# 3-RT5572-WLAN.net
KiCad netlist of a schematic drawn in Altium Designer
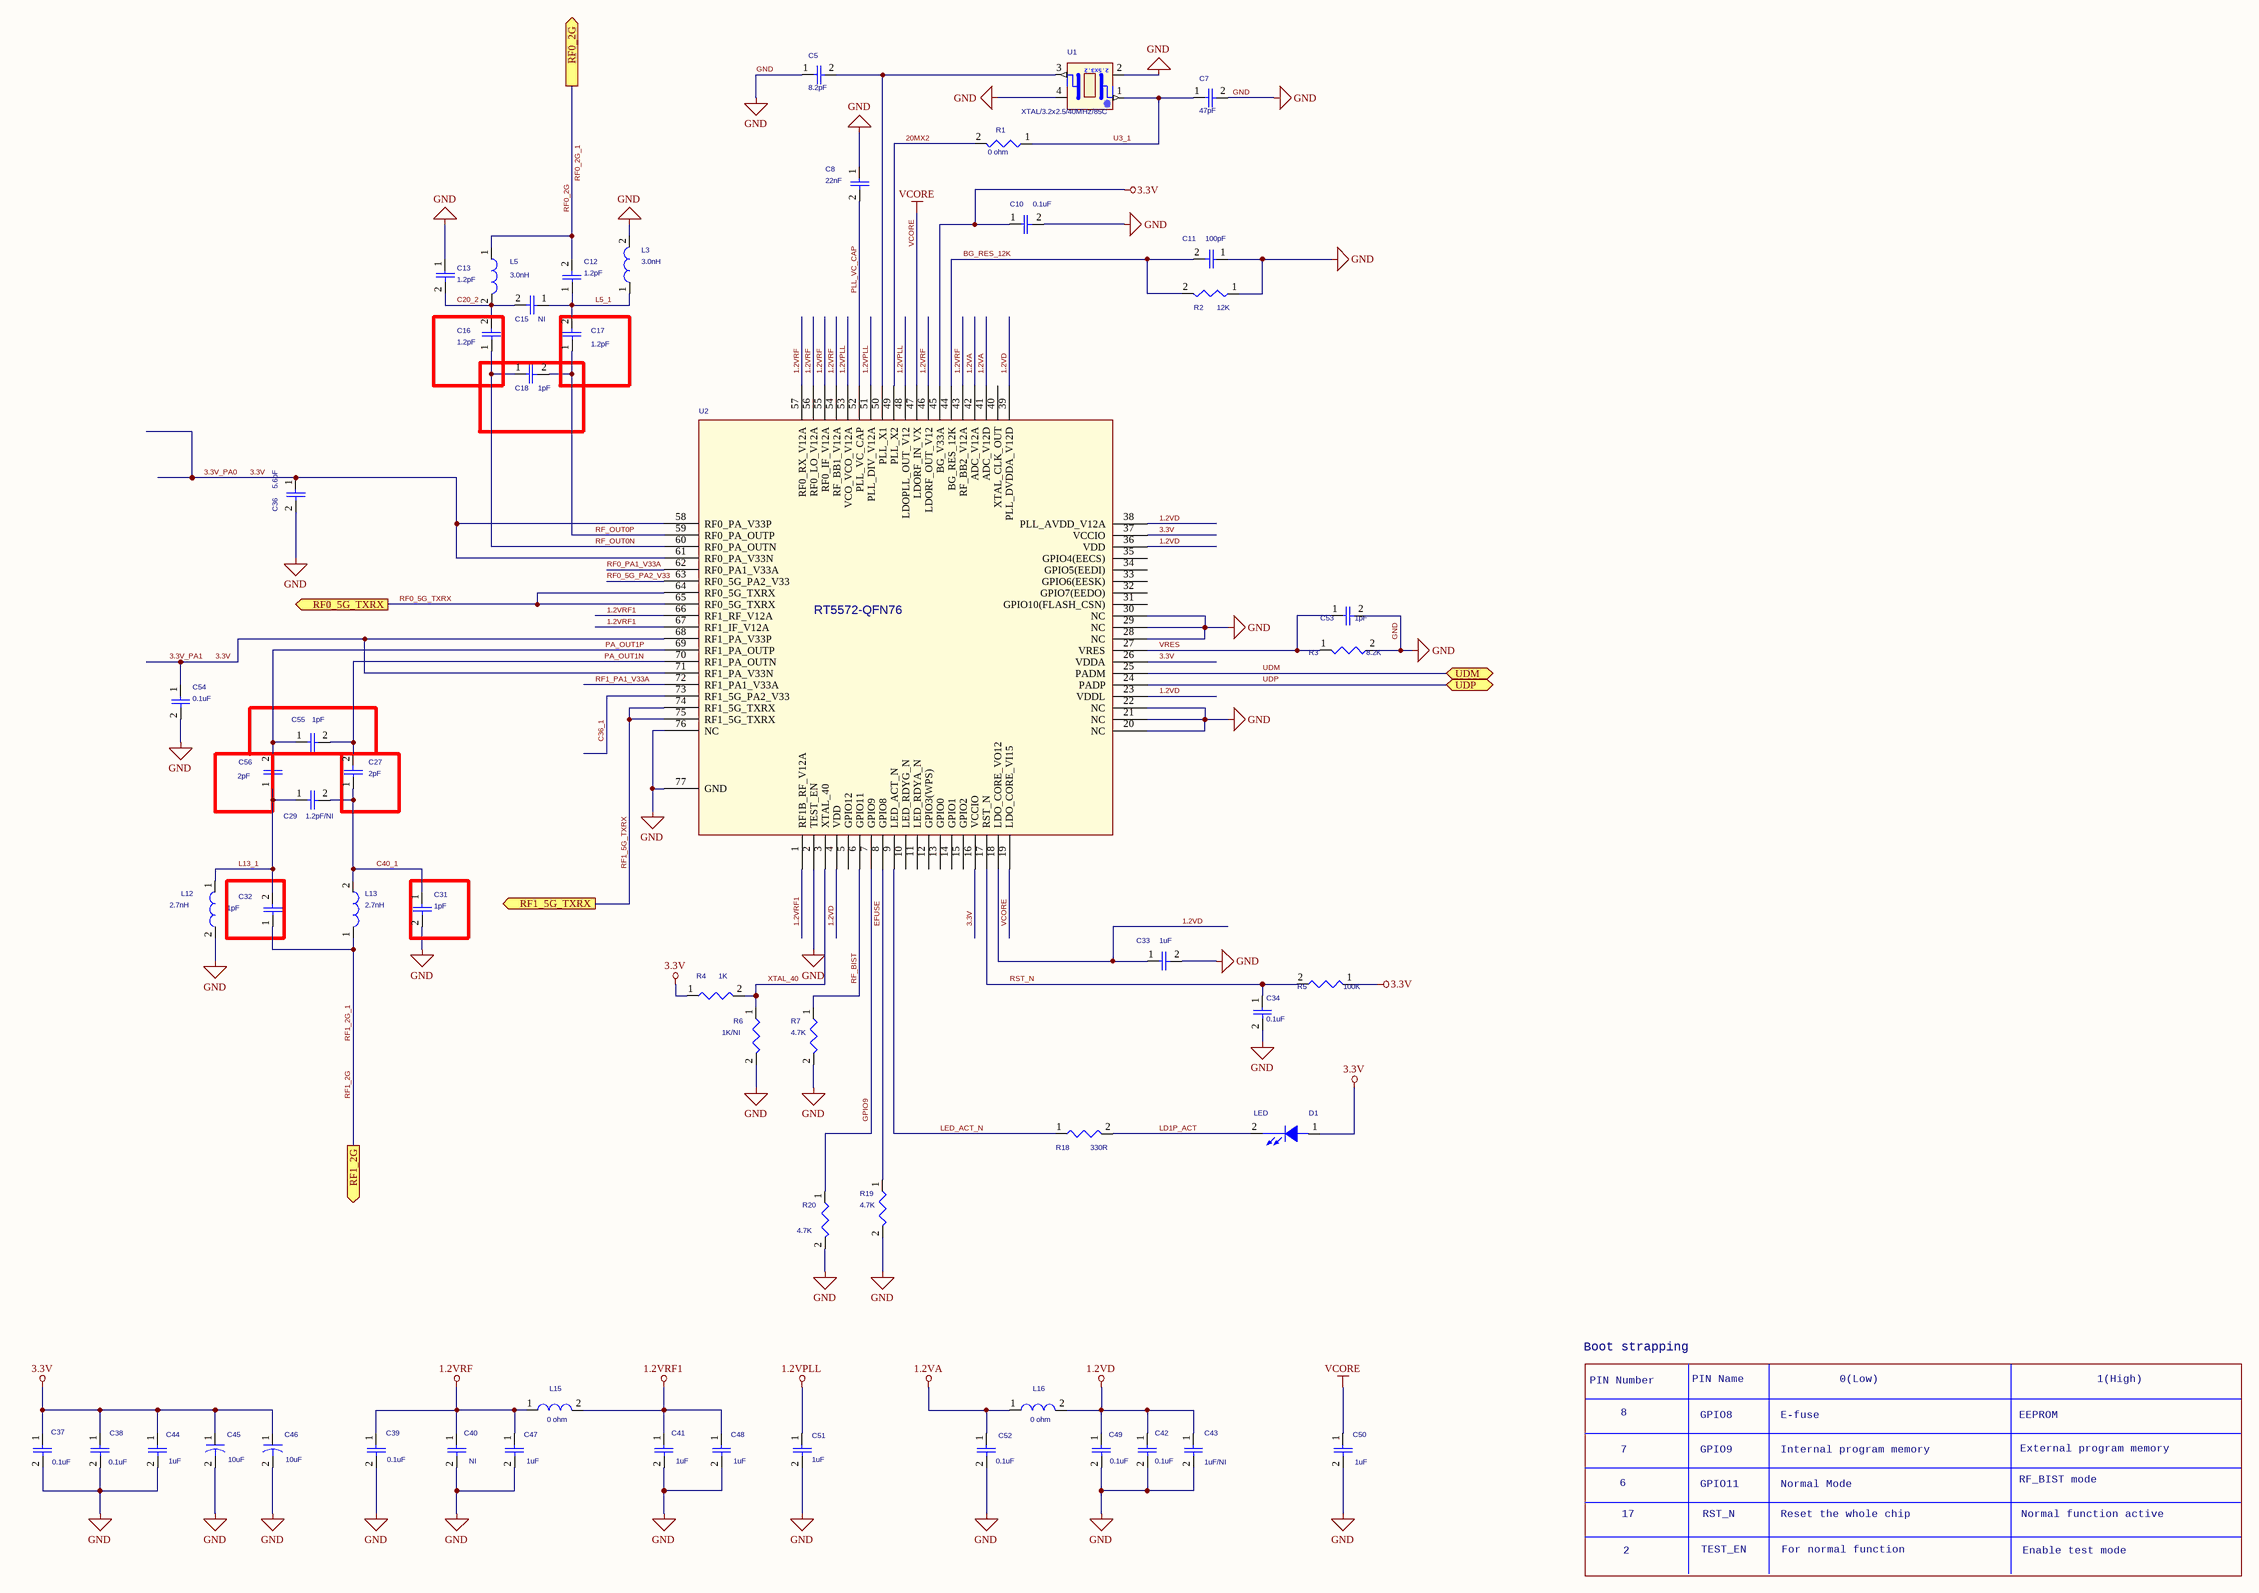
[diagram p0: 3-RT5572-WLAN.SchDoc]

(export (version "E")
  (design (tool "Eeschema 10.0.6"))
  (components
    (comp (ref "C5") (value "8.2pF") (footprint "0402") (libsource (lib "*") (part "CAP/0402")))
    (comp (ref "C7") (value "47pF") (footprint "0402") (libsource (lib "*") (part "CAP/0402")))
    (comp (ref "C8") (value "22nF") (footprint "0402") (libsource (lib "*") (part "CAP/0402")))
    (comp (ref "C10") (value "0.1uF") (footprint "0402") (libsource (lib "*") (part "CAP/0402")))
    (comp (ref "C11") (value "100pF") (footprint "0402") (libsource (lib "*") (part "CAP/0402")))
    (comp (ref "C12") (value "1.2pF") (footprint "0402") (libsource (lib "*") (part "CAP/0402")))
    (comp (ref "C13") (value "1.2pF") (footprint "0402") (libsource (lib "*") (part "CAP/0402")))
    (comp (ref "C15") (value "NI") (footprint "0402") (libsource (lib "*") (part "CAP/0402")))
    (comp (ref "C16") (value "1.2pF") (footprint "0402") (libsource (lib "*") (part "CAP/0402")))
    (comp (ref "C17") (value "1.2pF") (footprint "0402") (libsource (lib "*") (part "CAP/0402")))
    (comp (ref "C18") (value "1pF") (footprint "0402") (libsource (lib "*") (part "CAP/0402")))
    (comp (ref "C27") (value "2pF") (footprint "0402") (libsource (lib "*") (part "CAP/0402")))
    (comp (ref "C29") (value "1.2pF/NI") (footprint "0402") (libsource (lib "*") (part "CAP/0402")))
    (comp (ref "C31") (value "1pF") (footprint "0402") (libsource (lib "*") (part "CAP/0402")))
    (comp (ref "C32") (value "1pF") (footprint "0402") (libsource (lib "*") (part "CAP/0402")))
    (comp (ref "C33") (value "1uF") (footprint "0402") (libsource (lib "*") (part "CAP/0402")))
    (comp (ref "C34") (value "0.1uF") (footprint "0402") (libsource (lib "*") (part "CAP/0402")))
    (comp (ref "C36") (value "5.6pF") (footprint "0402") (libsource (lib "*") (part "CAP/0402")))
    (comp (ref "C37") (value "0.1uF") (footprint "0402") (libsource (lib "*") (part "CAP/0402")))
    (comp (ref "C38") (value "0.1uF") (footprint "0402") (libsource (lib "*") (part "CAP/0402")))
    (comp (ref "C39") (value "0.1uF") (footprint "0402") (libsource (lib "*") (part "CAP/0402")))
    (comp (ref "C40") (value "NI") (footprint "0402") (libsource (lib "*") (part "CAP/0402")))
    (comp (ref "C41") (value "1uF") (footprint "0402") (libsource (lib "*") (part "CAP/0402")))
    (comp (ref "C42") (value "0.1uF") (footprint "0402") (libsource (lib "*") (part "CAP/0402")))
    (comp (ref "C43") (value "1uF/NI") (footprint "0402") (libsource (lib "*") (part "CAP/0402")))
    (comp (ref "C44") (value "1uF") (footprint "0402") (libsource (lib "*") (part "CAP/0402")))
    (comp (ref "C45") (value "10uF") (libsource (lib "*") (part "CAP/0603")))
    (comp (ref "C46") (value "10uF") (libsource (lib "*") (part "CAP/0603")))
    (comp (ref "C47") (value "1uF") (footprint "0402") (libsource (lib "*") (part "CAP/0402")))
    (comp (ref "C48") (value "1uF") (footprint "0402") (libsource (lib "*") (part "CAP/0402")))
    (comp (ref "C49") (value "0.1uF") (footprint "0402") (libsource (lib "*") (part "CAP/0402")))
    (comp (ref "C50") (value "1uF") (footprint "0402") (libsource (lib "*") (part "CAP/0402")))
    (comp (ref "C51") (value "1uF") (footprint "0402") (libsource (lib "*") (part "CAP/0402")))
    (comp (ref "C52") (value "0.1uF") (footprint "0402") (libsource (lib "*") (part "CAP/0402")))
    (comp (ref "C53") (value "1pF") (footprint "0402") (libsource (lib "*") (part "CAP/0402")))
    (comp (ref "C54") (value "0.1uF") (footprint "0402") (libsource (lib "*") (part "CAP/0402")))
    (comp (ref "C55") (value "1pF") (footprint "0402") (libsource (lib "*") (part "CAP/0402")))
    (comp (ref "C56") (value "2pF") (footprint "0402") (libsource (lib "*") (part "CAP/0402")))
    (comp (ref "D1") (value "LED") (footprint "0603") (libsource (lib "*") (part "LED/0603")))
    (comp (ref "L3") (value "3.0nH") (footprint "0402") (libsource (lib "") (part "L/0402_1")))
    (comp (ref "L5") (value "3.0nH") (footprint "0402") (libsource (lib "") (part "L/0402_1")))
    (comp (ref "L12") (value "2.7nH") (footprint "0402") (libsource (lib "*") (part "L/0402_0")))
    (comp (ref "L13") (value "2.7nH") (footprint "0402") (libsource (lib "*") (part "L/0402")))
    (comp (ref "L15") (value "0 ohm") (footprint "0402") (libsource (lib "") (part "L/0402_1")))
    (comp (ref "L16") (value "0 ohm") (footprint "0402") (libsource (lib "") (part "L/0402_1")))
    (comp (ref "R1") (value "0 ohm") (footprint "0402") (libsource (lib "*") (part "RES/0402_1_Dup1")))
    (comp (ref "R2") (value "12K") (footprint "0402") (libsource (lib "*") (part "RES/0402_1_Dup1")))
    (comp (ref "R3") (value "8.2K") (footprint "0402") (libsource (lib "*") (part "RES/0402_2")))
    (comp (ref "R4") (value "1K") (footprint "0402") (libsource (lib "*") (part "RES/0402_1_Dup2")))
    (comp (ref "R5") (value "100K") (footprint "0402") (libsource (lib "*") (part "RES/0402_1_Dup1")))
    (comp (ref "R6") (value "1K/NI") (footprint "0402") (libsource (lib "*") (part "RES/0402_1_Dup2")))
    (comp (ref "R7") (value "4.7K") (footprint "0402") (libsource (lib "*") (part "RES/0402_1_Dup2")))
    (comp (ref "R18") (value "330R") (footprint "0402") (libsource (lib "*") (part "RES/0402_1")))
    (comp (ref "R19") (value "4.7K") (footprint "0402") (libsource (lib "*") (part "RES/0402_1_Dup2")))
    (comp (ref "R20") (value "4.7K") (footprint "0402") (libsource (lib "*") (part "RES/0402_1_Dup2")))
    (comp (ref "U1")
      (value "XTAL/3.2x2.5/40MHz/85C")
      (footprint "XTAL-SMD/3.2X2.5")
      (libsource (lib "*") (part "XTAL_2.5"))
    )
    (comp (ref "U2") (value "RT5572-QFN76") (libsource (lib "*") (part "RT5572_5")))
  )
  (nets
    (net (code "1") (name "/20MX2") (class "Default")
      (node (ref "R1") (pin "2") (pinfunction "2_2") (pintype "passive"))
      (node (ref "U2") (pin "49") (pinfunction "PLL_X2_49") (pintype "passive"))
    )
    (net (code "2") (name "/BG_RES_12K") (class "Default")
      (node (ref "C11") (pin "2") (pinfunction "2_2") (pintype "passive"))
      (node (ref "R2") (pin "2") (pinfunction "2_2") (pintype "passive"))
      (node (ref "U2") (pin "44") (pinfunction "BG_RES_12K_44") (pintype "passive"))
    )
    (net (code "3") (name "/C20_2") (class "Default")
      (node (ref "C13") (pin "2") (pinfunction "2_2") (pintype "passive"))
      (node (ref "C15") (pin "2") (pinfunction "2_2") (pintype "passive"))
      (node (ref "C16") (pin "2") (pinfunction "2_2") (pintype "passive"))
      (node (ref "L5") (pin "2") (pinfunction "2_2") (pintype "passive"))
    )
    (net (code "4") (name "/C36_1") (class "Default")
      (node (ref "U2") (pin "73") (pinfunction "RF1_5G_PA2_V33_73") (pintype "passive"))
    )
    (net (code "5") (name "/C40_1") (class "Default")
      (node (ref "C27") (pin "1") (pinfunction "1_1") (pintype "passive"))
      (node (ref "C29") (pin "2") (pinfunction "2_2") (pintype "passive"))
      (node (ref "C31") (pin "1") (pinfunction "1_1") (pintype "passive"))
      (node (ref "L13") (pin "2") (pinfunction "2_2") (pintype "passive"))
    )
    (net (code "6") (name "/EFUSE") (class "Default")
      (node (ref "R19") (pin "1") (pinfunction "1_1") (pintype "passive"))
      (node (ref "U2") (pin "8") (pinfunction "GPIO8_8") (pintype "passive"))
    )
    (net (code "7") (name "/GPIO9") (class "Default")
      (node (ref "R20") (pin "1") (pinfunction "1_1") (pintype "passive"))
      (node (ref "U2") (pin "7") (pinfunction "GPIO9_7") (pintype "passive"))
    )
    (net (code "8") (name "/L5_1") (class "Default")
      (node (ref "C12") (pin "1") (pinfunction "1_1") (pintype "passive"))
      (node (ref "C15") (pin "1") (pinfunction "1_1") (pintype "passive"))
      (node (ref "C17") (pin "2") (pinfunction "2_2") (pintype "passive"))
      (node (ref "L3") (pin "1") (pinfunction "1_1") (pintype "passive"))
    )
    (net (code "9") (name "/L13_1") (class "Default")
      (node (ref "C29") (pin "1") (pinfunction "1_1") (pintype "passive"))
      (node (ref "C32") (pin "2") (pinfunction "2_2") (pintype "passive"))
      (node (ref "C56") (pin "1") (pinfunction "1_1") (pintype "passive"))
      (node (ref "L12") (pin "1") (pinfunction "1_1") (pintype "passive"))
    )
    (net (code "10") (name "/LD1P_ACT") (class "Default")
      (node (ref "D1") (pin "2") (pinfunction "CATHODE_2") (pintype "passive"))
      (node (ref "R18") (pin "2") (pinfunction "2_2") (pintype "passive"))
    )
    (net (code "11") (name "/LED_ACT_N") (class "Default")
      (node (ref "R18") (pin "1") (pinfunction "1_1") (pintype "passive"))
      (node (ref "U2") (pin "9") (pinfunction "LED_ACT_N_9") (pintype "passive"))
    )
    (net (code "12") (name "/PA_OUT1N") (class "Default")
      (node (ref "C27") (pin "2") (pinfunction "2_2") (pintype "passive"))
      (node (ref "C55") (pin "2") (pinfunction "2_2") (pintype "passive"))
      (node (ref "U2") (pin "70") (pinfunction "RF1_PA_OUTN_70") (pintype "passive"))
    )
    (net (code "13") (name "/PA_OUT1P") (class "Default")
      (node (ref "C55") (pin "1") (pinfunction "1_1") (pintype "passive"))
      (node (ref "C56") (pin "2") (pinfunction "2_2") (pintype "passive"))
      (node (ref "U2") (pin "69") (pinfunction "RF1_PA_OUTP_69") (pintype "passive"))
    )
    (net (code "14") (name "/PLL_VC_CAP") (class "Default")
      (node (ref "C8") (pin "2") (pinfunction "2_2") (pintype "passive"))
      (node (ref "U2") (pin "52") (pinfunction "PLL_VC_CAP_52") (pintype "passive"))
    )
    (net (code "15") (name "/RF0_2G") (class "Default")
      (node (ref "C12") (pin "2") (pinfunction "2_2") (pintype "passive"))
      (node (ref "L5") (pin "1") (pinfunction "1_1") (pintype "passive"))
    )
    (net (code "16") (name "/RF0_5G_PA2_V33") (class "Default")
      (node (ref "U2") (pin "63") (pinfunction "RF0_5G_PA2_V33_63") (pintype "passive"))
    )
    (net (code "17") (name "/RF0_5G_TXRX") (class "Default")
      (node (ref "U2") (pin "64") (pinfunction "RF0_5G_TXRX_64") (pintype "passive"))
      (node (ref "U2") (pin "65") (pinfunction "RF0_5G_TXRX_65") (pintype "passive"))
    )
    (net (code "18") (name "/RF0_PA1_V33A") (class "Default")
      (node (ref "U2") (pin "62") (pinfunction "RF0_PA1_V33A_62") (pintype "passive"))
    )
    (net (code "19") (name "/RF1_2G") (class "Default")
      (node (ref "C32") (pin "1") (pinfunction "1_1") (pintype "passive"))
      (node (ref "L13") (pin "1") (pinfunction "1_1") (pintype "passive"))
    )
    (net (code "20") (name "/RF1_5G_TXRX") (class "Default")
      (node (ref "U2") (pin "74") (pinfunction "RF1_5G_TXRX_74") (pintype "passive"))
      (node (ref "U2") (pin "75") (pinfunction "RF1_5G_TXRX_75") (pintype "passive"))
    )
    (net (code "21") (name "/RF1_PA1_V33A") (class "Default")
      (node (ref "U2") (pin "72") (pinfunction "RF1_PA1_V33A_72") (pintype "passive"))
    )
    (net (code "22") (name "/RF_BIST") (class "Default")
      (node (ref "R7") (pin "1") (pinfunction "1_1") (pintype "passive"))
      (node (ref "U2") (pin "6") (pinfunction "GPIO11_6") (pintype "passive"))
    )
    (net (code "23") (name "/RF_OUT0N") (class "Default")
      (node (ref "C16") (pin "1") (pinfunction "1_1") (pintype "passive"))
      (node (ref "C18") (pin "1") (pinfunction "1_1") (pintype "passive"))
      (node (ref "U2") (pin "60") (pinfunction "RF0_PA_OUTN_60") (pintype "passive"))
    )
    (net (code "24") (name "/RF_OUT0P") (class "Default")
      (node (ref "C17") (pin "1") (pinfunction "1_1") (pintype "passive"))
      (node (ref "C18") (pin "2") (pinfunction "2_2") (pintype "passive"))
      (node (ref "U2") (pin "59") (pinfunction "RF0_PA_OUTP_59") (pintype "passive"))
    )
    (net (code "25") (name "/RST_N") (class "Default")
      (node (ref "C34") (pin "1") (pinfunction "1_1") (pintype "passive"))
      (node (ref "R5") (pin "2") (pinfunction "2_2") (pintype "passive"))
      (node (ref "U2") (pin "17") (pinfunction "RST_N_17") (pintype "passive"))
    )
    (net (code "26") (name "/U3_1") (class "Default")
      (node (ref "C7") (pin "1") (pinfunction "1_1") (pintype "passive"))
      (node (ref "R1") (pin "1") (pinfunction "1_1") (pintype "passive"))
      (node (ref "U1") (pin "1") (pinfunction "X1_1") (pintype "output"))
    )
    (net (code "27") (name "/UDM") (class "Default")
      (node (ref "U2") (pin "25") (pinfunction "PADM_25") (pintype "passive"))
    )
    (net (code "28") (name "/UDP") (class "Default")
      (node (ref "U2") (pin "24") (pinfunction "PADP_24") (pintype "passive"))
    )
    (net (code "29") (name "/VRES") (class "Default")
      (node (ref "C53") (pin "1") (pinfunction "1_1") (pintype "passive"))
      (node (ref "R3") (pin "1") (pinfunction "1_1") (pintype "passive"))
      (node (ref "U2") (pin "27") (pinfunction "VRES_27") (pintype "passive"))
    )
    (net (code "30") (name "/XTAL_40") (class "Default")
      (node (ref "R4") (pin "2") (pinfunction "2_2") (pintype "passive"))
      (node (ref "R6") (pin "1") (pinfunction "1_1") (pintype "passive"))
      (node (ref "U2") (pin "3") (pinfunction "XTAL_40_3") (pintype "passive"))
    )
    (net (code "31") (name "1.2VA") (class "Default")
      (node (ref "C52") (pin "1") (pinfunction "1_1") (pintype "passive"))
      (node (ref "L16") (pin "1") (pinfunction "1_1") (pintype "passive"))
      (node (ref "U2") (pin "41") (pinfunction "ADC_V12D_41") (pintype "passive"))
      (node (ref "U2") (pin "42") (pinfunction "ADC_V12A_42") (pintype "passive"))
    )
    (net (code "32") (name "1.2VD") (class "Default")
      (node (ref "C33") (pin "1") (pinfunction "1_1") (pintype "passive"))
      (node (ref "C42") (pin "1") (pinfunction "1_1") (pintype "passive"))
      (node (ref "C43") (pin "1") (pinfunction "1_1") (pintype "passive"))
      (node (ref "C49") (pin "1") (pinfunction "1_1") (pintype "passive"))
      (node (ref "L16") (pin "2") (pinfunction "2_2") (pintype "passive"))
      (node (ref "U2") (pin "18") (pinfunction "LDO_CORE_VO12_18") (pintype "passive"))
      (node (ref "U2") (pin "23") (pinfunction "VDDL_23") (pintype "passive"))
      (node (ref "U2") (pin "36") (pinfunction "VDD_36") (pintype "passive"))
      (node (ref "U2") (pin "38") (pinfunction "PLL_AVDD_V12A_38") (pintype "passive"))
      (node (ref "U2") (pin "39") (pinfunction "PLL_DVDDA_V12D_39") (pintype "passive"))
      (node (ref "U2") (pin "4") (pinfunction "VDD_4") (pintype "passive"))
    )
    (net (code "33") (name "1.2VPLL") (class "Default")
      (node (ref "C51") (pin "1") (pinfunction "1_1") (pintype "passive"))
      (node (ref "U2") (pin "48") (pinfunction "LDOPLL_OUT_V12_48") (pintype "passive"))
      (node (ref "U2") (pin "51") (pinfunction "PLL_DIV_V12A_51") (pintype "passive"))
      (node (ref "U2") (pin "53") (pinfunction "VCO_VCO_V12A_53") (pintype "passive"))
    )
    (net (code "34") (name "1.2VRF") (class "Default")
      (node (ref "C39") (pin "1") (pinfunction "1_1") (pintype "passive"))
      (node (ref "C40") (pin "1") (pinfunction "1_1") (pintype "passive"))
      (node (ref "C47") (pin "1") (pinfunction "1_1") (pintype "passive"))
      (node (ref "L15") (pin "1") (pinfunction "1_1") (pintype "passive"))
      (node (ref "U2") (pin "43") (pinfunction "RF_BB2_V12A_43") (pintype "passive"))
      (node (ref "U2") (pin "46") (pinfunction "LDORF_OUT_V12_46") (pintype "passive"))
      (node (ref "U2") (pin "54") (pinfunction "RF_BB1_V12A_54") (pintype "passive"))
      (node (ref "U2") (pin "55") (pinfunction "RF0_IF_V12A_55") (pintype "passive"))
      (node (ref "U2") (pin "56") (pinfunction "RF0_LO_V12A_56") (pintype "passive"))
      (node (ref "U2") (pin "57") (pinfunction "RF0_RX_V12A_57") (pintype "passive"))
    )
    (net (code "35") (name "1.2VRF1") (class "Default")
      (node (ref "C41") (pin "1") (pinfunction "1_1") (pintype "passive"))
      (node (ref "C48") (pin "1") (pinfunction "1_1") (pintype "passive"))
      (node (ref "L15") (pin "2") (pinfunction "2_2") (pintype "passive"))
      (node (ref "U2") (pin "1") (pinfunction "RF1B_RF_V12A_1") (pintype "passive"))
      (node (ref "U2") (pin "66") (pinfunction "RF1_RF_V12A_66") (pintype "passive"))
      (node (ref "U2") (pin "67") (pinfunction "RF1_IF_V12A_67") (pintype "passive"))
    )
    (net (code "36") (name "3.3V") (class "Default")
      (node (ref "C10") (pin "1") (pinfunction "1_1") (pintype "passive"))
      (node (ref "C36") (pin "1") (pinfunction "1_1") (pintype "passive"))
      (node (ref "C37") (pin "1") (pinfunction "1_1") (pintype "passive"))
      (node (ref "C38") (pin "1") (pinfunction "1_1") (pintype "passive"))
      (node (ref "C44") (pin "1") (pinfunction "1_1") (pintype "passive"))
      (node (ref "C45") (pin "1") (pinfunction "1_1") (pintype "passive"))
      (node (ref "C46") (pin "1") (pinfunction "1_1") (pintype "passive"))
      (node (ref "C54") (pin "1") (pinfunction "1_1") (pintype "passive"))
      (node (ref "D1") (pin "1") (pinfunction "ANODE_1") (pintype "passive"))
      (node (ref "R4") (pin "1") (pinfunction "1_1") (pintype "passive"))
      (node (ref "R5") (pin "1") (pinfunction "1_1") (pintype "passive"))
      (node (ref "U2") (pin "16") (pinfunction "VCCIO_16") (pintype "passive"))
      (node (ref "U2") (pin "26") (pinfunction "VDDA_26") (pintype "passive"))
      (node (ref "U2") (pin "37") (pinfunction "VCCIO_37") (pintype "passive"))
      (node (ref "U2") (pin "45") (pinfunction "BG_V33A_45") (pintype "passive"))
      (node (ref "U2") (pin "58") (pinfunction "RF0_PA_V33P_58") (pintype "passive"))
      (node (ref "U2") (pin "61") (pinfunction "RF0_PA_V33N_61") (pintype "passive"))
      (node (ref "U2") (pin "68") (pinfunction "RF1_PA_V33P_68") (pintype "passive"))
      (node (ref "U2") (pin "71") (pinfunction "RF1_PA_V33N_71") (pintype "passive"))
    )
    (net (code "37") (name "GND") (class "Default")
      (node (ref "C10") (pin "2") (pinfunction "2_2") (pintype "passive"))
      (node (ref "C11") (pin "1") (pinfunction "1_1") (pintype "passive"))
      (node (ref "C13") (pin "1") (pinfunction "1_1") (pintype "passive"))
      (node (ref "C31") (pin "2") (pinfunction "2_2") (pintype "passive"))
      (node (ref "C33") (pin "2") (pinfunction "2_2") (pintype "passive"))
      (node (ref "C34") (pin "2") (pinfunction "2_2") (pintype "passive"))
      (node (ref "C36") (pin "2") (pinfunction "2_2") (pintype "passive"))
      (node (ref "C37") (pin "2") (pinfunction "2_2") (pintype "passive"))
      (node (ref "C38") (pin "2") (pinfunction "2_2") (pintype "passive"))
      (node (ref "C39") (pin "2") (pinfunction "2_2") (pintype "passive"))
      (node (ref "C40") (pin "2") (pinfunction "2_2") (pintype "passive"))
      (node (ref "C41") (pin "2") (pinfunction "2_2") (pintype "passive"))
      (node (ref "C42") (pin "2") (pinfunction "2_2") (pintype "passive"))
      (node (ref "C43") (pin "2") (pinfunction "2_2") (pintype "passive"))
      (node (ref "C44") (pin "2") (pinfunction "2_2") (pintype "passive"))
      (node (ref "C45") (pin "2") (pinfunction "2_2") (pintype "passive"))
      (node (ref "C46") (pin "2") (pinfunction "2_2") (pintype "passive"))
      (node (ref "C47") (pin "2") (pinfunction "2_2") (pintype "passive"))
      (node (ref "C48") (pin "2") (pinfunction "2_2") (pintype "passive"))
      (node (ref "C49") (pin "2") (pinfunction "2_2") (pintype "passive"))
      (node (ref "C5") (pin "1") (pinfunction "1_1") (pintype "passive"))
      (node (ref "C50") (pin "2") (pinfunction "2_2") (pintype "passive"))
      (node (ref "C51") (pin "2") (pinfunction "2_2") (pintype "passive"))
      (node (ref "C52") (pin "2") (pinfunction "2_2") (pintype "passive"))
      (node (ref "C53") (pin "2") (pinfunction "2_2") (pintype "passive"))
      (node (ref "C54") (pin "2") (pinfunction "2_2") (pintype "passive"))
      (node (ref "C7") (pin "2") (pinfunction "2_2") (pintype "passive"))
      (node (ref "C8") (pin "1") (pinfunction "1_1") (pintype "passive"))
      (node (ref "L12") (pin "2") (pinfunction "2_2") (pintype "passive"))
      (node (ref "L3") (pin "2") (pinfunction "2_2") (pintype "passive"))
      (node (ref "R19") (pin "2") (pinfunction "2_2") (pintype "passive"))
      (node (ref "R2") (pin "1") (pinfunction "1_1") (pintype "passive"))
      (node (ref "R20") (pin "2") (pinfunction "2_2") (pintype "passive"))
      (node (ref "R3") (pin "2") (pinfunction "2_2") (pintype "passive"))
      (node (ref "R6") (pin "2") (pinfunction "2_2") (pintype "passive"))
      (node (ref "R7") (pin "2") (pinfunction "2_2") (pintype "passive"))
      (node (ref "U1") (pin "2") (pinfunction "NC_2") (pintype "passive"))
      (node (ref "U1") (pin "4") (pinfunction "NC_4") (pintype "passive"))
      (node (ref "U2") (pin "2") (pinfunction "TEST_EN_2") (pintype "passive"))
      (node (ref "U2") (pin "20") (pinfunction "NC_20") (pintype "passive"))
      (node (ref "U2") (pin "21") (pinfunction "NC_21") (pintype "passive"))
      (node (ref "U2") (pin "22") (pinfunction "NC_22") (pintype "passive"))
      (node (ref "U2") (pin "28") (pinfunction "NC_28") (pintype "passive"))
      (node (ref "U2") (pin "29") (pinfunction "NC_29") (pintype "passive"))
      (node (ref "U2") (pin "30") (pinfunction "NC_30") (pintype "passive"))
      (node (ref "U2") (pin "76") (pinfunction "NC_76") (pintype "passive"))
      (node (ref "U2") (pin "77") (pinfunction "GND_77") (pintype "passive"))
    )
    (net (code "38") (name "Net-(U1-X2)") (class "Default")
      (node (ref "C5") (pin "2") (pinfunction "2_2") (pintype "passive"))
      (node (ref "U1") (pin "3") (pinfunction "X2_3") (pintype "output"))
      (node (ref "U2") (pin "50") (pinfunction "PLL_X1_50") (pintype "passive"))
    )
    (net (code "39") (name "VCORE") (class "Default")
      (node (ref "C50") (pin "1") (pinfunction "1_1") (pintype "passive"))
      (node (ref "U2") (pin "19") (pinfunction "LDO_CORE_VI15_19") (pintype "passive"))
      (node (ref "U2") (pin "47") (pinfunction "LDORF_IN_VX_47") (pintype "passive"))
    )
    (net (code "40") (name "unconnected-(U2-GPIO0-Pad13)") (class "Default")
      (node (ref "U2") (pin "13") (pinfunction "GPIO0_13") (pintype "passive"))
    )
    (net (code "41") (name "unconnected-(U2-GPIO1-Pad14)") (class "Default")
      (node (ref "U2") (pin "14") (pinfunction "GPIO1_14") (pintype "passive"))
    )
    (net (code "42") (name "unconnected-(U2-GPIO2-Pad15)") (class "Default")
      (node (ref "U2") (pin "15") (pinfunction "GPIO2_15") (pintype "passive"))
    )
    (net (code "43") (name "unconnected-(U2-GPIO3(WPS)-Pad12)") (class "Default")
      (node (ref "U2") (pin "12") (pinfunction "GPIO3(WPS)_12") (pintype "passive"))
    )
    (net (code "44") (name "unconnected-(U2-GPIO4(EECS)-Pad35)") (class "Default")
      (node (ref "U2") (pin "35") (pinfunction "GPIO4(EECS)_35") (pintype "passive"))
    )
    (net (code "45") (name "unconnected-(U2-GPIO5(EEDI)-Pad34)") (class "Default")
      (node (ref "U2") (pin "34") (pinfunction "GPIO5(EEDI)_34") (pintype "passive"))
    )
    (net (code "46") (name "unconnected-(U2-GPIO6(EESK)-Pad33)") (class "Default")
      (node (ref "U2") (pin "33") (pinfunction "GPIO6(EESK)_33") (pintype "passive"))
    )
    (net (code "47") (name "unconnected-(U2-GPIO7(EEDO)-Pad32)") (class "Default")
      (node (ref "U2") (pin "32") (pinfunction "GPIO7(EEDO)_32") (pintype "passive"))
    )
    (net (code "48") (name "unconnected-(U2-GPIO10(FLASH_CSN)-Pad31)") (class "Default")
      (node (ref "U2") (pin "31") (pinfunction "GPIO10(FLASH_CSN)_31") (pintype "passive"))
    )
    (net (code "49") (name "unconnected-(U2-GPIO12-Pad5)") (class "Default")
      (node (ref "U2") (pin "5") (pinfunction "GPIO12_5") (pintype "passive"))
    )
    (net (code "50") (name "unconnected-(U2-LED_RDYA_N-Pad11)") (class "Default")
      (node (ref "U2") (pin "11") (pinfunction "LED_RDYA_N_11") (pintype "passive"))
    )
    (net (code "51") (name "unconnected-(U2-LED_RDYG_N-Pad10)") (class "Default")
      (node (ref "U2") (pin "10") (pinfunction "LED_RDYG_N_10") (pintype "passive"))
    )
    (net (code "52") (name "unconnected-(U2-XTAL_CLK_OUT-Pad40)") (class "Default")
      (node (ref "U2") (pin "40") (pinfunction "XTAL_CLK_OUT_40") (pintype "passive"))
    )
  )
)
